# DDR3_Power.net
KiCad netlist of a schematic drawn in Altium Designer
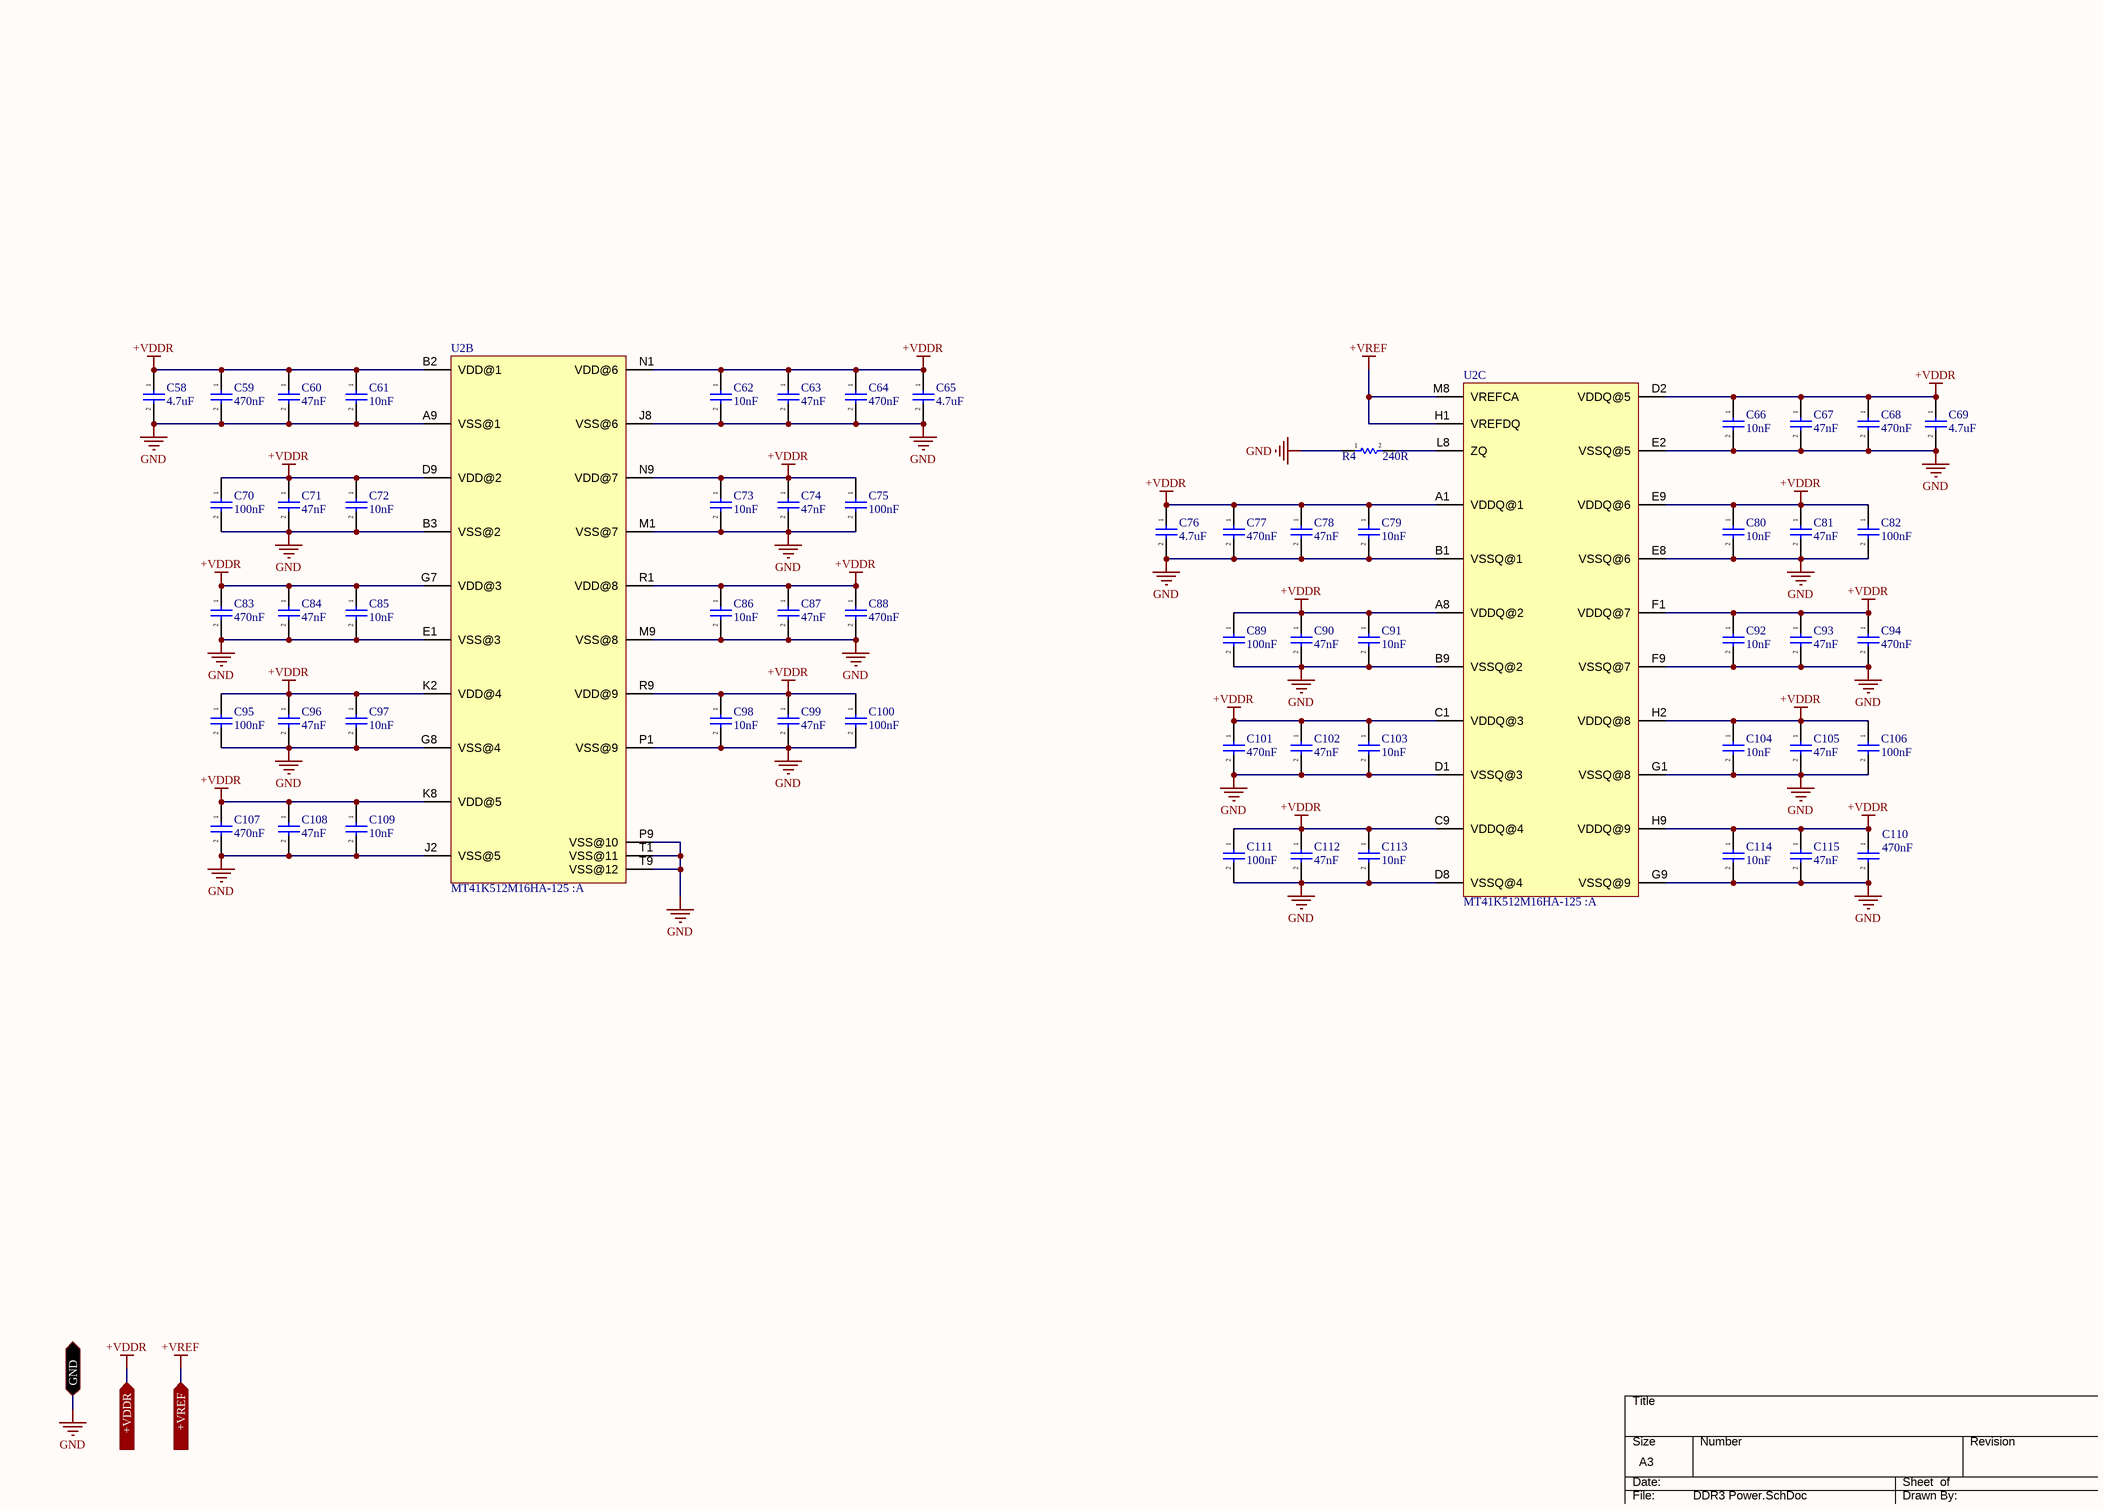
[diagram p0: DDR3 Power.SchDoc]

(export (version "E")
  (design (tool "Eeschema 10.0.6"))
  (components
    (comp (ref "C58")
      (value "4.7uF")
      (footprint "CAP_0805")
      (description "Generic SMT Ceramic Capacitor")
      (libsource (lib "Symbols") (part "CAP_CER"))
    )
    (comp (ref "C59")
      (value "470nF")
      (footprint "CAP_0402")
      (description "Generic SMT Ceramic Capacitor")
      (libsource (lib "Symbols") (part "CAP_CER"))
    )
    (comp (ref "C60")
      (value "47nF")
      (footprint "CAP_0201")
      (description "Generic SMT Ceramic Capacitor")
      (libsource (lib "Symbols") (part "CAP_CER"))
    )
    (comp (ref "C61")
      (value "10nF")
      (footprint "CAP_0201")
      (description "Generic SMT Ceramic Capacitor")
      (libsource (lib "Symbols") (part "CAP_CER"))
    )
    (comp (ref "C62")
      (value "10nF")
      (footprint "CAP_0201")
      (description "Generic SMT Ceramic Capacitor")
      (libsource (lib "Symbols") (part "CAP_CER"))
    )
    (comp (ref "C63")
      (value "47nF")
      (footprint "CAP_0201")
      (description "Generic SMT Ceramic Capacitor")
      (libsource (lib "Symbols") (part "CAP_CER"))
    )
    (comp (ref "C64")
      (value "470nF")
      (footprint "CAP_0402")
      (description "Generic SMT Ceramic Capacitor")
      (libsource (lib "Symbols") (part "CAP_CER"))
    )
    (comp (ref "C65")
      (value "4.7uF")
      (footprint "CAP_0805")
      (description "Generic SMT Ceramic Capacitor")
      (libsource (lib "Symbols") (part "CAP_CER"))
    )
    (comp (ref "C66")
      (value "10nF")
      (footprint "CAP_0201")
      (description "Generic SMT Ceramic Capacitor")
      (libsource (lib "Symbols") (part "CAP_CER"))
    )
    (comp (ref "C67")
      (value "47nF")
      (footprint "CAP_0201")
      (description "Generic SMT Ceramic Capacitor")
      (libsource (lib "Symbols") (part "CAP_CER"))
    )
    (comp (ref "C68")
      (value "470nF")
      (footprint "CAP_0402")
      (description "Generic SMT Ceramic Capacitor")
      (libsource (lib "Symbols") (part "CAP_CER"))
    )
    (comp (ref "C69")
      (value "4.7uF")
      (footprint "CAP_0805")
      (description "Generic SMT Ceramic Capacitor")
      (libsource (lib "Symbols") (part "CAP_CER"))
    )
    (comp (ref "C70")
      (value "100nF")
      (footprint "CAP_0402")
      (description "Generic SMT Ceramic Capacitor")
      (libsource (lib "Symbols") (part "CAP_CER"))
    )
    (comp (ref "C71")
      (value "47nF")
      (footprint "CAP_0201")
      (description "Generic SMT Ceramic Capacitor")
      (libsource (lib "Symbols") (part "CAP_CER"))
    )
    (comp (ref "C72")
      (value "10nF")
      (footprint "CAP_0201")
      (description "Generic SMT Ceramic Capacitor")
      (libsource (lib "Symbols") (part "CAP_CER"))
    )
    (comp (ref "C73")
      (value "10nF")
      (footprint "CAP_0201")
      (description "Generic SMT Ceramic Capacitor")
      (libsource (lib "Symbols") (part "CAP_CER"))
    )
    (comp (ref "C74")
      (value "47nF")
      (footprint "CAP_0201")
      (description "Generic SMT Ceramic Capacitor")
      (libsource (lib "Symbols") (part "CAP_CER"))
    )
    (comp (ref "C75")
      (value "100nF")
      (footprint "CAP_0402")
      (description "Generic SMT Ceramic Capacitor")
      (libsource (lib "Symbols") (part "CAP_CER"))
    )
    (comp (ref "C76")
      (value "4.7uF")
      (footprint "CAP_0805")
      (description "Generic SMT Ceramic Capacitor")
      (libsource (lib "Symbols") (part "CAP_CER"))
    )
    (comp (ref "C77")
      (value "470nF")
      (footprint "CAP_0402")
      (description "Generic SMT Ceramic Capacitor")
      (libsource (lib "Symbols") (part "CAP_CER"))
    )
    (comp (ref "C78")
      (value "47nF")
      (footprint "CAP_0201")
      (description "Generic SMT Ceramic Capacitor")
      (libsource (lib "Symbols") (part "CAP_CER"))
    )
    (comp (ref "C79")
      (value "10nF")
      (footprint "CAP_0201")
      (description "Generic SMT Ceramic Capacitor")
      (libsource (lib "Symbols") (part "CAP_CER"))
    )
    (comp (ref "C80")
      (value "10nF")
      (footprint "CAP_0201")
      (description "Generic SMT Ceramic Capacitor")
      (libsource (lib "Symbols") (part "CAP_CER"))
    )
    (comp (ref "C81")
      (value "47nF")
      (footprint "CAP_0201")
      (description "Generic SMT Ceramic Capacitor")
      (libsource (lib "Symbols") (part "CAP_CER"))
    )
    (comp (ref "C82")
      (value "100nF")
      (footprint "CAP_0402")
      (description "Generic SMT Ceramic Capacitor")
      (libsource (lib "Symbols") (part "CAP_CER"))
    )
    (comp (ref "C83")
      (value "470nF")
      (footprint "CAP_0402")
      (description "Generic SMT Ceramic Capacitor")
      (libsource (lib "Symbols") (part "CAP_CER"))
    )
    (comp (ref "C84")
      (value "47nF")
      (footprint "CAP_0201")
      (description "Generic SMT Ceramic Capacitor")
      (libsource (lib "Symbols") (part "CAP_CER"))
    )
    (comp (ref "C85")
      (value "10nF")
      (footprint "CAP_0201")
      (description "Generic SMT Ceramic Capacitor")
      (libsource (lib "Symbols") (part "CAP_CER"))
    )
    (comp (ref "C86")
      (value "10nF")
      (footprint "CAP_0201")
      (description "Generic SMT Ceramic Capacitor")
      (libsource (lib "Symbols") (part "CAP_CER"))
    )
    (comp (ref "C87")
      (value "47nF")
      (footprint "CAP_0201")
      (description "Generic SMT Ceramic Capacitor")
      (libsource (lib "Symbols") (part "CAP_CER"))
    )
    (comp (ref "C88")
      (value "470nF")
      (footprint "CAP_0402")
      (description "Generic SMT Ceramic Capacitor")
      (libsource (lib "Symbols") (part "CAP_CER"))
    )
    (comp (ref "C89")
      (value "100nF")
      (footprint "CAP_0402")
      (description "Generic SMT Ceramic Capacitor")
      (libsource (lib "Symbols") (part "CAP_CER"))
    )
    (comp (ref "C90")
      (value "47nF")
      (footprint "CAP_0201")
      (description "Generic SMT Ceramic Capacitor")
      (libsource (lib "Symbols") (part "CAP_CER"))
    )
    (comp (ref "C91")
      (value "10nF")
      (footprint "CAP_0201")
      (description "Generic SMT Ceramic Capacitor")
      (libsource (lib "Symbols") (part "CAP_CER"))
    )
    (comp (ref "C92")
      (value "10nF")
      (footprint "CAP_0201")
      (description "Generic SMT Ceramic Capacitor")
      (libsource (lib "Symbols") (part "CAP_CER"))
    )
    (comp (ref "C93")
      (value "47nF")
      (footprint "CAP_0201")
      (description "Generic SMT Ceramic Capacitor")
      (libsource (lib "Symbols") (part "CAP_CER"))
    )
    (comp (ref "C94")
      (value "470nF")
      (footprint "CAP_0402")
      (description "Generic SMT Ceramic Capacitor")
      (libsource (lib "Symbols") (part "CAP_CER"))
    )
    (comp (ref "C95")
      (value "100nF")
      (footprint "CAP_0402")
      (description "Generic SMT Ceramic Capacitor")
      (libsource (lib "Symbols") (part "CAP_CER"))
    )
    (comp (ref "C96")
      (value "47nF")
      (footprint "CAP_0201")
      (description "Generic SMT Ceramic Capacitor")
      (libsource (lib "Symbols") (part "CAP_CER"))
    )
    (comp (ref "C97")
      (value "10nF")
      (footprint "CAP_0201")
      (description "Generic SMT Ceramic Capacitor")
      (libsource (lib "Symbols") (part "CAP_CER"))
    )
    (comp (ref "C98")
      (value "10nF")
      (footprint "CAP_0201")
      (description "Generic SMT Ceramic Capacitor")
      (libsource (lib "Symbols") (part "CAP_CER"))
    )
    (comp (ref "C99")
      (value "47nF")
      (footprint "CAP_0201")
      (description "Generic SMT Ceramic Capacitor")
      (libsource (lib "Symbols") (part "CAP_CER"))
    )
    (comp (ref "C100")
      (value "100nF")
      (footprint "CAP_0402")
      (description "Generic SMT Ceramic Capacitor")
      (libsource (lib "Symbols") (part "CAP_CER"))
    )
    (comp (ref "C101")
      (value "470nF")
      (footprint "CAP_0402")
      (description "Generic SMT Ceramic Capacitor")
      (libsource (lib "Symbols") (part "CAP_CER"))
    )
    (comp (ref "C102")
      (value "47nF")
      (footprint "CAP_0201")
      (description "Generic SMT Ceramic Capacitor")
      (libsource (lib "Symbols") (part "CAP_CER"))
    )
    (comp (ref "C103")
      (value "10nF")
      (footprint "CAP_0201")
      (description "Generic SMT Ceramic Capacitor")
      (libsource (lib "Symbols") (part "CAP_CER"))
    )
    (comp (ref "C104")
      (value "10nF")
      (footprint "CAP_0201")
      (description "Generic SMT Ceramic Capacitor")
      (libsource (lib "Symbols") (part "CAP_CER"))
    )
    (comp (ref "C105")
      (value "47nF")
      (footprint "CAP_0201")
      (description "Generic SMT Ceramic Capacitor")
      (libsource (lib "Symbols") (part "CAP_CER"))
    )
    (comp (ref "C106")
      (value "100nF")
      (footprint "CAP_0402")
      (description "Generic SMT Ceramic Capacitor")
      (libsource (lib "Symbols") (part "CAP_CER"))
    )
    (comp (ref "C107")
      (value "470nF")
      (footprint "CAP_0402")
      (description "Generic SMT Ceramic Capacitor")
      (libsource (lib "Symbols") (part "CAP_CER"))
    )
    (comp (ref "C108")
      (value "47nF")
      (footprint "CAP_0201")
      (description "Generic SMT Ceramic Capacitor")
      (libsource (lib "Symbols") (part "CAP_CER"))
    )
    (comp (ref "C109")
      (value "10nF")
      (footprint "CAP_0201")
      (description "Generic SMT Ceramic Capacitor")
      (libsource (lib "Symbols") (part "CAP_CER"))
    )
    (comp (ref "C110")
      (value "470nF")
      (footprint "CAP_0402")
      (description "Generic SMT Ceramic Capacitor")
      (libsource (lib "Symbols") (part "CAP_CER"))
    )
    (comp (ref "C111")
      (value "100nF")
      (footprint "CAP_0402")
      (description "Generic SMT Ceramic Capacitor")
      (libsource (lib "Symbols") (part "CAP_CER"))
    )
    (comp (ref "C112")
      (value "47nF")
      (footprint "CAP_0201")
      (description "Generic SMT Ceramic Capacitor")
      (libsource (lib "Symbols") (part "CAP_CER"))
    )
    (comp (ref "C113")
      (value "10nF")
      (footprint "CAP_0201")
      (description "Generic SMT Ceramic Capacitor")
      (libsource (lib "Symbols") (part "CAP_CER"))
    )
    (comp (ref "C114")
      (value "10nF")
      (footprint "CAP_0201")
      (description "Generic SMT Ceramic Capacitor")
      (libsource (lib "Symbols") (part "CAP_CER"))
    )
    (comp (ref "C115")
      (value "47nF")
      (footprint "CAP_0201")
      (description "Generic SMT Ceramic Capacitor")
      (libsource (lib "Symbols") (part "CAP_CER"))
    )
    (comp (ref "R4")
      (value "240R")
      (footprint "RES_0402")
      (description "Resistor")
      (fields (field (name "POWER") "1/8W") (field (name "TOLERANCE") "1%"))
      (libsource (lib "Symbols") (part "RESISTOR"))
    )
    (comp (ref "U2")
      (value "MT41K512M16HA-125 :A")
      (footprint "FBGA-96")
      (description "DRAM 8G 1.35V 512Mx16 800 MHz DDR3 0C-90C")
      (fields (field (name "MFR") "Alliance Memory"))
      (libsource (lib "CryptLib") (part "IC_MT41K512M16HA-125"))
    )
  )
  (nets
    (net (code "1") (name "+VDDR") (class "Default")
      (node (ref "C100") (pin "1") (pinfunction "1_1") (pintype "passive"))
      (node (ref "C101") (pin "1") (pinfunction "1_1") (pintype "passive"))
      (node (ref "C102") (pin "1") (pinfunction "1_1") (pintype "passive"))
      (node (ref "C103") (pin "1") (pinfunction "1_1") (pintype "passive"))
      (node (ref "C104") (pin "1") (pinfunction "1_1") (pintype "passive"))
      (node (ref "C105") (pin "1") (pinfunction "1_1") (pintype "passive"))
      (node (ref "C106") (pin "1") (pinfunction "1_1") (pintype "passive"))
      (node (ref "C107") (pin "1") (pinfunction "1_1") (pintype "passive"))
      (node (ref "C108") (pin "1") (pinfunction "1_1") (pintype "passive"))
      (node (ref "C109") (pin "1") (pinfunction "1_1") (pintype "passive"))
      (node (ref "C110") (pin "1") (pinfunction "1_1") (pintype "passive"))
      (node (ref "C111") (pin "1") (pinfunction "1_1") (pintype "passive"))
      (node (ref "C112") (pin "1") (pinfunction "1_1") (pintype "passive"))
      (node (ref "C113") (pin "1") (pinfunction "1_1") (pintype "passive"))
      (node (ref "C114") (pin "1") (pinfunction "1_1") (pintype "passive"))
      (node (ref "C115") (pin "1") (pinfunction "1_1") (pintype "passive"))
      (node (ref "C58") (pin "1") (pinfunction "1_1") (pintype "passive"))
      (node (ref "C59") (pin "1") (pinfunction "1_1") (pintype "passive"))
      (node (ref "C60") (pin "1") (pinfunction "1_1") (pintype "passive"))
      (node (ref "C61") (pin "1") (pinfunction "1_1") (pintype "passive"))
      (node (ref "C62") (pin "1") (pinfunction "1_1") (pintype "passive"))
      (node (ref "C63") (pin "1") (pinfunction "1_1") (pintype "passive"))
      (node (ref "C64") (pin "1") (pinfunction "1_1") (pintype "passive"))
      (node (ref "C65") (pin "1") (pinfunction "1_1") (pintype "passive"))
      (node (ref "C66") (pin "1") (pinfunction "1_1") (pintype "passive"))
      (node (ref "C67") (pin "1") (pinfunction "1_1") (pintype "passive"))
      (node (ref "C68") (pin "1") (pinfunction "1_1") (pintype "passive"))
      (node (ref "C69") (pin "1") (pinfunction "1_1") (pintype "passive"))
      (node (ref "C70") (pin "1") (pinfunction "1_1") (pintype "passive"))
      (node (ref "C71") (pin "1") (pinfunction "1_1") (pintype "passive"))
      (node (ref "C72") (pin "1") (pinfunction "1_1") (pintype "passive"))
      (node (ref "C73") (pin "1") (pinfunction "1_1") (pintype "passive"))
      (node (ref "C74") (pin "1") (pinfunction "1_1") (pintype "passive"))
      (node (ref "C75") (pin "1") (pinfunction "1_1") (pintype "passive"))
      (node (ref "C76") (pin "1") (pinfunction "1_1") (pintype "passive"))
      (node (ref "C77") (pin "1") (pinfunction "1_1") (pintype "passive"))
      (node (ref "C78") (pin "1") (pinfunction "1_1") (pintype "passive"))
      (node (ref "C79") (pin "1") (pinfunction "1_1") (pintype "passive"))
      (node (ref "C80") (pin "1") (pinfunction "1_1") (pintype "passive"))
      (node (ref "C81") (pin "1") (pinfunction "1_1") (pintype "passive"))
      (node (ref "C82") (pin "1") (pinfunction "1_1") (pintype "passive"))
      (node (ref "C83") (pin "1") (pinfunction "1_1") (pintype "passive"))
      (node (ref "C84") (pin "1") (pinfunction "1_1") (pintype "passive"))
      (node (ref "C85") (pin "1") (pinfunction "1_1") (pintype "passive"))
      (node (ref "C86") (pin "1") (pinfunction "1_1") (pintype "passive"))
      (node (ref "C87") (pin "1") (pinfunction "1_1") (pintype "passive"))
      (node (ref "C88") (pin "1") (pinfunction "1_1") (pintype "passive"))
      (node (ref "C89") (pin "1") (pinfunction "1_1") (pintype "passive"))
      (node (ref "C90") (pin "1") (pinfunction "1_1") (pintype "passive"))
      (node (ref "C91") (pin "1") (pinfunction "1_1") (pintype "passive"))
      (node (ref "C92") (pin "1") (pinfunction "1_1") (pintype "passive"))
      (node (ref "C93") (pin "1") (pinfunction "1_1") (pintype "passive"))
      (node (ref "C94") (pin "1") (pinfunction "1_1") (pintype "passive"))
      (node (ref "C95") (pin "1") (pinfunction "1_1") (pintype "passive"))
      (node (ref "C96") (pin "1") (pinfunction "1_1") (pintype "passive"))
      (node (ref "C97") (pin "1") (pinfunction "1_1") (pintype "passive"))
      (node (ref "C98") (pin "1") (pinfunction "1_1") (pintype "passive"))
      (node (ref "C99") (pin "1") (pinfunction "1_1") (pintype "passive"))
      (node (ref "U2") (pin "A1") (pinfunction "VDDQ@1_A1") (pintype "power_in"))
      (node (ref "U2") (pin "A8") (pinfunction "VDDQ@2_A8") (pintype "power_in"))
      (node (ref "U2") (pin "B2") (pinfunction "VDD@1_B2") (pintype "power_in"))
      (node (ref "U2") (pin "C1") (pinfunction "VDDQ@3_C1") (pintype "power_in"))
      (node (ref "U2") (pin "C9") (pinfunction "VDDQ@4_C9") (pintype "power_in"))
      (node (ref "U2") (pin "D2") (pinfunction "VDDQ@5_D2") (pintype "power_in"))
      (node (ref "U2") (pin "D9") (pinfunction "VDD@2_D9") (pintype "power_in"))
      (node (ref "U2") (pin "E9") (pinfunction "VDDQ@6_E9") (pintype "power_in"))
      (node (ref "U2") (pin "F1") (pinfunction "VDDQ@7_F1") (pintype "power_in"))
      (node (ref "U2") (pin "G7") (pinfunction "VDD@3_G7") (pintype "power_in"))
      (node (ref "U2") (pin "H2") (pinfunction "VDDQ@8_H2") (pintype "power_in"))
      (node (ref "U2") (pin "H9") (pinfunction "VDDQ@9_H9") (pintype "power_in"))
      (node (ref "U2") (pin "K2") (pinfunction "VDD@4_K2") (pintype "power_in"))
      (node (ref "U2") (pin "K8") (pinfunction "VDD@5_K8") (pintype "power_in"))
      (node (ref "U2") (pin "N1") (pinfunction "VDD@6_N1") (pintype "power_in"))
      (node (ref "U2") (pin "N9") (pinfunction "VDD@7_N9") (pintype "power_in"))
      (node (ref "U2") (pin "R1") (pinfunction "VDD@8_R1") (pintype "power_in"))
      (node (ref "U2") (pin "R9") (pinfunction "VDD@9_R9") (pintype "power_in"))
    )
    (net (code "2") (name "+VREF") (class "Default")
      (node (ref "U2") (pin "H1") (pinfunction "VREFDQ_H1") (pintype "power_in"))
      (node (ref "U2") (pin "M8") (pinfunction "VREFCA_M8") (pintype "power_in"))
    )
    (net (code "3") (name "GND") (class "Default")
      (node (ref "C100") (pin "2") (pinfunction "2_2") (pintype "passive"))
      (node (ref "C101") (pin "2") (pinfunction "2_2") (pintype "passive"))
      (node (ref "C102") (pin "2") (pinfunction "2_2") (pintype "passive"))
      (node (ref "C103") (pin "2") (pinfunction "2_2") (pintype "passive"))
      (node (ref "C104") (pin "2") (pinfunction "2_2") (pintype "passive"))
      (node (ref "C105") (pin "2") (pinfunction "2_2") (pintype "passive"))
      (node (ref "C106") (pin "2") (pinfunction "2_2") (pintype "passive"))
      (node (ref "C107") (pin "2") (pinfunction "2_2") (pintype "passive"))
      (node (ref "C108") (pin "2") (pinfunction "2_2") (pintype "passive"))
      (node (ref "C109") (pin "2") (pinfunction "2_2") (pintype "passive"))
      (node (ref "C110") (pin "2") (pinfunction "2_2") (pintype "passive"))
      (node (ref "C111") (pin "2") (pinfunction "2_2") (pintype "passive"))
      (node (ref "C112") (pin "2") (pinfunction "2_2") (pintype "passive"))
      (node (ref "C113") (pin "2") (pinfunction "2_2") (pintype "passive"))
      (node (ref "C114") (pin "2") (pinfunction "2_2") (pintype "passive"))
      (node (ref "C115") (pin "2") (pinfunction "2_2") (pintype "passive"))
      (node (ref "C58") (pin "2") (pinfunction "2_2") (pintype "passive"))
      (node (ref "C59") (pin "2") (pinfunction "2_2") (pintype "passive"))
      (node (ref "C60") (pin "2") (pinfunction "2_2") (pintype "passive"))
      (node (ref "C61") (pin "2") (pinfunction "2_2") (pintype "passive"))
      (node (ref "C62") (pin "2") (pinfunction "2_2") (pintype "passive"))
      (node (ref "C63") (pin "2") (pinfunction "2_2") (pintype "passive"))
      (node (ref "C64") (pin "2") (pinfunction "2_2") (pintype "passive"))
      (node (ref "C65") (pin "2") (pinfunction "2_2") (pintype "passive"))
      (node (ref "C66") (pin "2") (pinfunction "2_2") (pintype "passive"))
      (node (ref "C67") (pin "2") (pinfunction "2_2") (pintype "passive"))
      (node (ref "C68") (pin "2") (pinfunction "2_2") (pintype "passive"))
      (node (ref "C69") (pin "2") (pinfunction "2_2") (pintype "passive"))
      (node (ref "C70") (pin "2") (pinfunction "2_2") (pintype "passive"))
      (node (ref "C71") (pin "2") (pinfunction "2_2") (pintype "passive"))
      (node (ref "C72") (pin "2") (pinfunction "2_2") (pintype "passive"))
      (node (ref "C73") (pin "2") (pinfunction "2_2") (pintype "passive"))
      (node (ref "C74") (pin "2") (pinfunction "2_2") (pintype "passive"))
      (node (ref "C75") (pin "2") (pinfunction "2_2") (pintype "passive"))
      (node (ref "C76") (pin "2") (pinfunction "2_2") (pintype "passive"))
      (node (ref "C77") (pin "2") (pinfunction "2_2") (pintype "passive"))
      (node (ref "C78") (pin "2") (pinfunction "2_2") (pintype "passive"))
      (node (ref "C79") (pin "2") (pinfunction "2_2") (pintype "passive"))
      (node (ref "C80") (pin "2") (pinfunction "2_2") (pintype "passive"))
      (node (ref "C81") (pin "2") (pinfunction "2_2") (pintype "passive"))
      (node (ref "C82") (pin "2") (pinfunction "2_2") (pintype "passive"))
      (node (ref "C83") (pin "2") (pinfunction "2_2") (pintype "passive"))
      (node (ref "C84") (pin "2") (pinfunction "2_2") (pintype "passive"))
      (node (ref "C85") (pin "2") (pinfunction "2_2") (pintype "passive"))
      (node (ref "C86") (pin "2") (pinfunction "2_2") (pintype "passive"))
      (node (ref "C87") (pin "2") (pinfunction "2_2") (pintype "passive"))
      (node (ref "C88") (pin "2") (pinfunction "2_2") (pintype "passive"))
      (node (ref "C89") (pin "2") (pinfunction "2_2") (pintype "passive"))
      (node (ref "C90") (pin "2") (pinfunction "2_2") (pintype "passive"))
      (node (ref "C91") (pin "2") (pinfunction "2_2") (pintype "passive"))
      (node (ref "C92") (pin "2") (pinfunction "2_2") (pintype "passive"))
      (node (ref "C93") (pin "2") (pinfunction "2_2") (pintype "passive"))
      (node (ref "C94") (pin "2") (pinfunction "2_2") (pintype "passive"))
      (node (ref "C95") (pin "2") (pinfunction "2_2") (pintype "passive"))
      (node (ref "C96") (pin "2") (pinfunction "2_2") (pintype "passive"))
      (node (ref "C97") (pin "2") (pinfunction "2_2") (pintype "passive"))
      (node (ref "C98") (pin "2") (pinfunction "2_2") (pintype "passive"))
      (node (ref "C99") (pin "2") (pinfunction "2_2") (pintype "passive"))
      (node (ref "R4") (pin "1") (pinfunction "1_1") (pintype "passive"))
      (node (ref "U2") (pin "A9") (pinfunction "VSS@1_A9") (pintype "power_in"))
      (node (ref "U2") (pin "B1") (pinfunction "VSSQ@1_B1") (pintype "power_in"))
      (node (ref "U2") (pin "B3") (pinfunction "VSS@2_B3") (pintype "power_in"))
      (node (ref "U2") (pin "B9") (pinfunction "VSSQ@2_B9") (pintype "power_in"))
      (node (ref "U2") (pin "D1") (pinfunction "VSSQ@3_D1") (pintype "power_in"))
      (node (ref "U2") (pin "D8") (pinfunction "VSSQ@4_D8") (pintype "power_in"))
      (node (ref "U2") (pin "E1") (pinfunction "VSS@3_E1") (pintype "power_in"))
      (node (ref "U2") (pin "E2") (pinfunction "VSSQ@5_E2") (pintype "power_in"))
      (node (ref "U2") (pin "E8") (pinfunction "VSSQ@6_E8") (pintype "power_in"))
      (node (ref "U2") (pin "F9") (pinfunction "VSSQ@7_F9") (pintype "power_in"))
      (node (ref "U2") (pin "G1") (pinfunction "VSSQ@8_G1") (pintype "power_in"))
      (node (ref "U2") (pin "G8") (pinfunction "VSS@4_G8") (pintype "power_in"))
      (node (ref "U2") (pin "G9") (pinfunction "VSSQ@9_G9") (pintype "power_in"))
      (node (ref "U2") (pin "J2") (pinfunction "VSS@5_J2") (pintype "power_in"))
      (node (ref "U2") (pin "J8") (pinfunction "VSS@6_J8") (pintype "power_in"))
      (node (ref "U2") (pin "M1") (pinfunction "VSS@7_M1") (pintype "power_in"))
      (node (ref "U2") (pin "M9") (pinfunction "VSS@8_M9") (pintype "power_in"))
      (node (ref "U2") (pin "P1") (pinfunction "VSS@9_P1") (pintype "power_in"))
      (node (ref "U2") (pin "P9") (pinfunction "VSS@10_P9") (pintype "power_in"))
      (node (ref "U2") (pin "T1") (pinfunction "VSS@11_T1") (pintype "power_in"))
      (node (ref "U2") (pin "T9") (pinfunction "VSS@12_T9") (pintype "power_in"))
    )
    (net (code "4") (name "Net-(U2C-ZQ)") (class "Default")
      (node (ref "R4") (pin "2") (pinfunction "2_2") (pintype "passive"))
      (node (ref "U2") (pin "L8") (pinfunction "ZQ_L8") (pintype "passive"))
    )
  )
)
